# 01_MAIN.net
KiCad netlist of a schematic drawn in Altium Designer
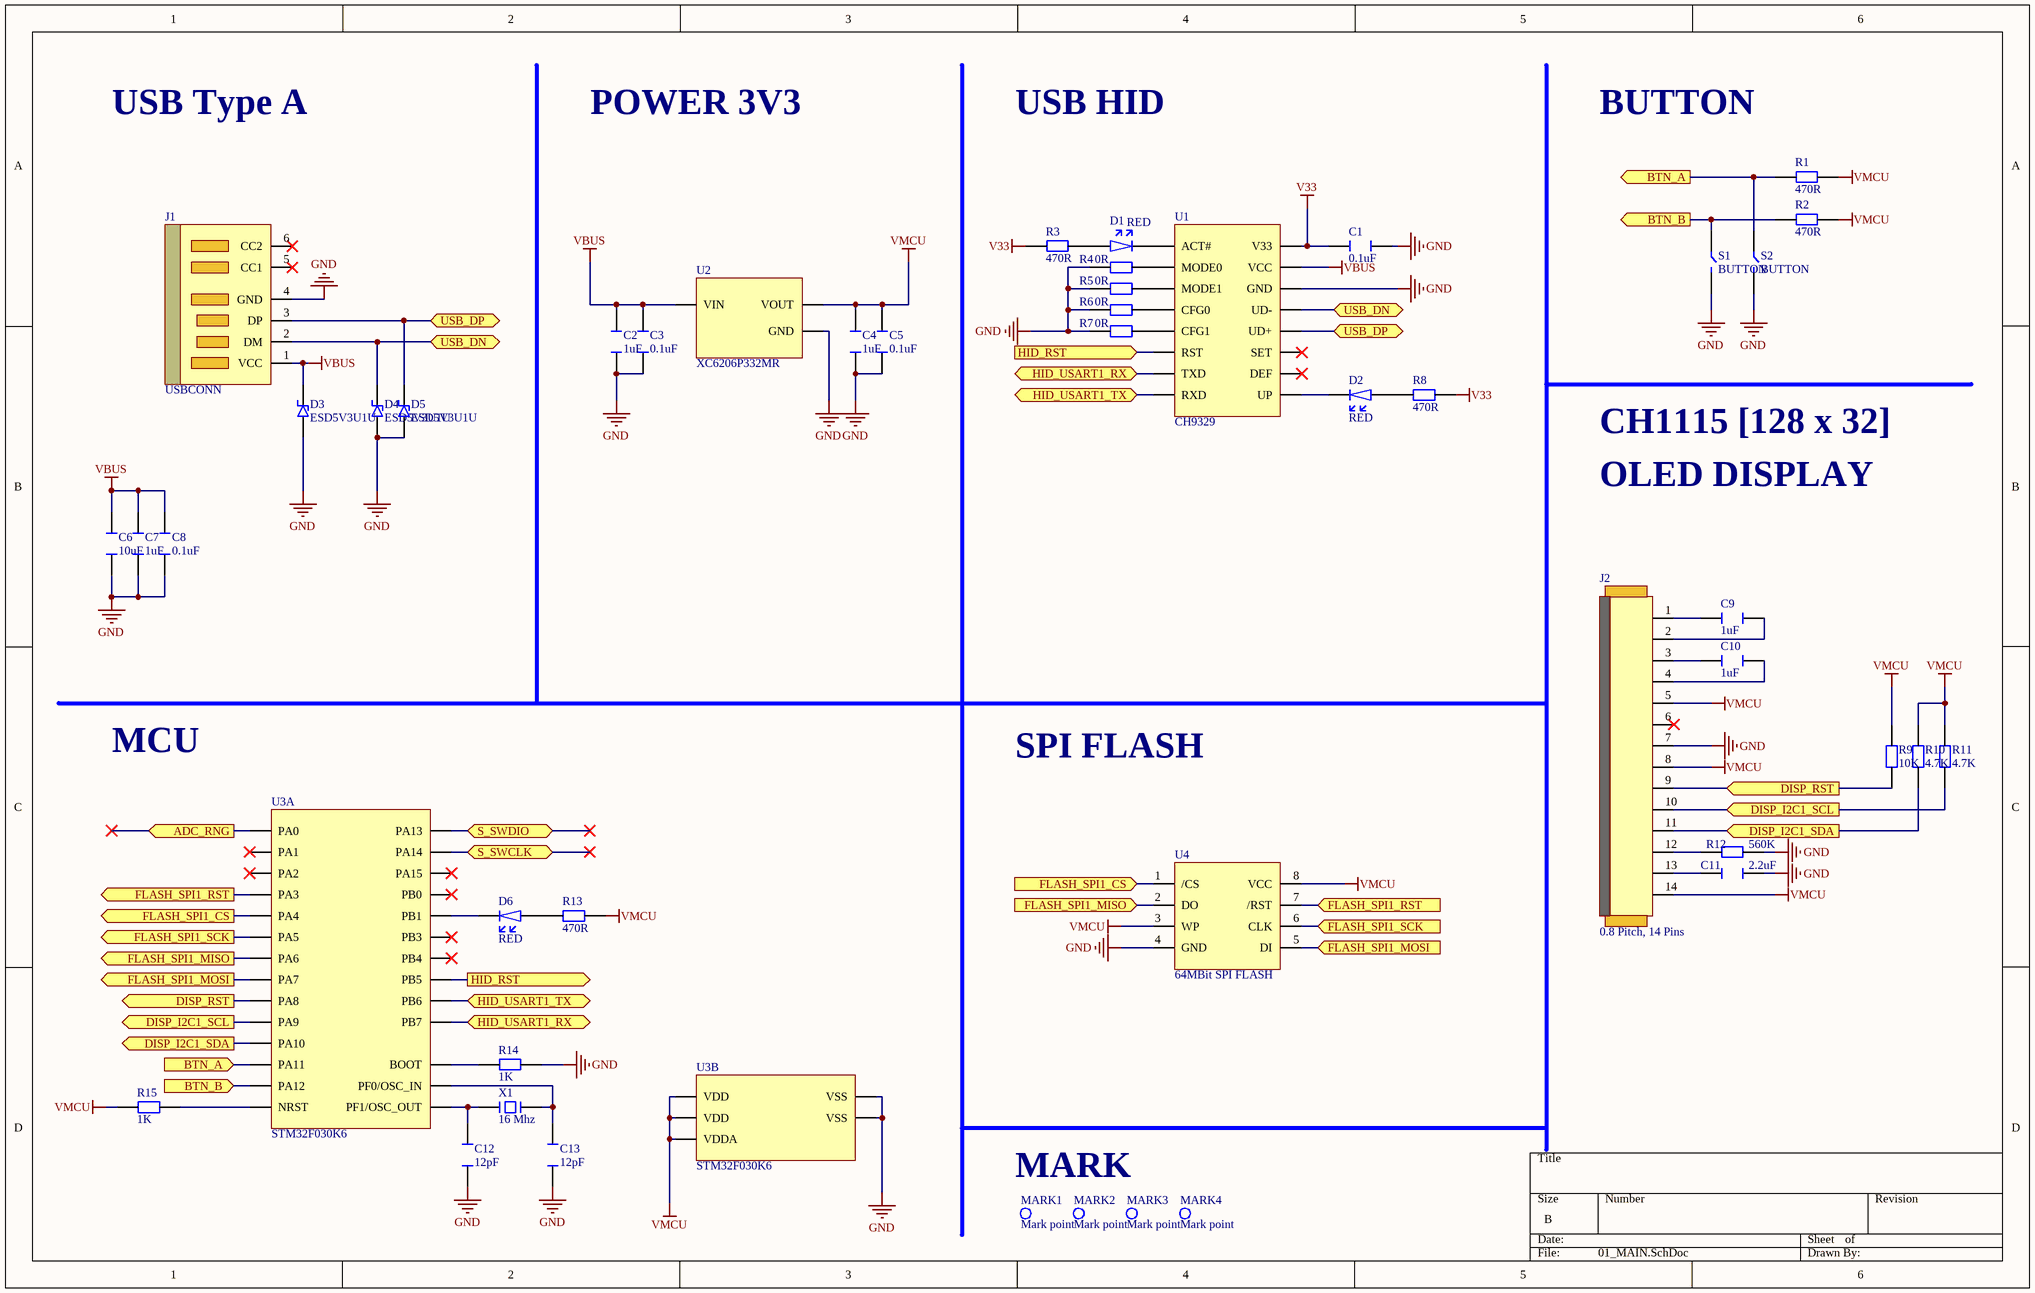
[diagram p0: 01_MAIN.SchDoc]

(export (version "E")
  (design (tool "Eeschema 10.0.6"))
  (components
    (comp (ref "C1") (value "0.1uF") (footprint "C0402") (libsource (lib "Cosmos") (part "C_0.1UF")))
    (comp (ref "C2") (value "1uF") (footprint "C0603") (libsource (lib "Cosmos") (part "C_1UF")))
    (comp (ref "C3") (value "0.1uF") (footprint "C0603") (libsource (lib "Cosmos") (part "C_0.1UF")))
    (comp (ref "C4") (value "1uF") (footprint "C0402") (libsource (lib "Cosmos") (part "C_1UF")))
    (comp (ref "C5") (value "0.1uF") (footprint "C0402") (libsource (lib "Cosmos") (part "C_0.1UF")))
    (comp (ref "C6") (value "10uF") (footprint "C0603") (libsource (lib "Cosmos") (part "C_10UF")))
    (comp (ref "C7") (value "1uF") (footprint "C0603") (libsource (lib "Cosmos") (part "C_1UF")))
    (comp (ref "C8") (value "0.1uF") (footprint "C0603") (libsource (lib "Cosmos") (part "C_0.1UF")))
    (comp (ref "C9") (value "1uF") (footprint "C0402") (libsource (lib "Cosmos") (part "C_1UF")))
    (comp (ref "C10") (value "1uF") (footprint "C0402") (libsource (lib "Cosmos") (part "C_1UF")))
    (comp (ref "C11") (value "2.2uF") (footprint "C0402") (libsource (lib "Cosmos") (part "C_2.2UF")))
    (comp (ref "C12") (value "12pF") (footprint "C0402") (libsource (lib "Cosmos") (part "C_12PF")))
    (comp (ref "C13") (value "12pF") (footprint "C0402") (libsource (lib "Cosmos") (part "C_12PF")))
    (comp (ref "D1") (value "RED") (footprint "LED0402") (libsource (lib "Cosmos") (part "LED_RED")))
    (comp (ref "D2") (value "RED") (footprint "LED0402") (libsource (lib "Cosmos") (part "LED_RED")))
    (comp (ref "D3")
      (value "ESD5V3U1U")
      (footprint "ESD5V3U1U")
      (libsource (lib "Cosmos") (part "ESD5V3U1U"))
    )
    (comp (ref "D4")
      (value "ESD5V3U1U")
      (footprint "ESD5V3U1U")
      (libsource (lib "Cosmos") (part "ESD5V3U1U"))
    )
    (comp (ref "D5")
      (value "ESD5V3U1U")
      (footprint "ESD5V3U1U")
      (libsource (lib "Cosmos") (part "ESD5V3U1U"))
    )
    (comp (ref "D6") (value "RED") (footprint "LED0402") (libsource (lib "Cosmos") (part "LED_RED")))
    (comp (ref "J1")
      (value "USBCONN")
      (footprint "USBAM_SNGLE_8PIN")
      (libsource (lib "Cosmos") (part "USBCONN"))
    )
    (comp (ref "J2")
      (value "0.8 Pitch, 14 Pins")
      (footprint "FPC-14PIN")
      (libsource (lib "Cosmos") (part "FPC_14PIN"))
    )
    (comp (ref "MARK1")
      (value "Mark point")
      (footprint "MARKPOINT")
      (libsource (lib "Earthquake") (part "MP"))
    )
    (comp (ref "MARK2")
      (value "Mark point")
      (footprint "MARKPOINT")
      (libsource (lib "Earthquake") (part "MP"))
    )
    (comp (ref "MARK3")
      (value "Mark point")
      (footprint "MARKPOINT")
      (libsource (lib "Earthquake") (part "MP"))
    )
    (comp (ref "MARK4")
      (value "Mark point")
      (footprint "MARKPOINT")
      (libsource (lib "Earthquake") (part "MP"))
    )
    (comp (ref "R1") (value "470R") (footprint "R0402") (libsource (lib "Cosmos") (part "R_470R")))
    (comp (ref "R2") (value "470R") (footprint "R0402") (libsource (lib "Cosmos") (part "R_470R")))
    (comp (ref "R3") (value "470R") (footprint "R0402") (libsource (lib "Cosmos") (part "R_470R")))
    (comp (ref "R4") (value "0R") (footprint "R0402") (libsource (lib "Cosmos") (part "R_0R")))
    (comp (ref "R5") (value "0R") (footprint "R0402") (libsource (lib "Cosmos") (part "R_0R")))
    (comp (ref "R6") (value "0R") (footprint "R0402") (libsource (lib "Cosmos") (part "R_0R")))
    (comp (ref "R7") (value "0R") (footprint "R0402") (libsource (lib "Cosmos") (part "R_0R")))
    (comp (ref "R8") (value "470R") (footprint "R0402") (libsource (lib "Cosmos") (part "R_470R")))
    (comp (ref "R9") (value "10K") (footprint "R0402") (libsource (lib "Cosmos") (part "R_10K")))
    (comp (ref "R10") (value "4.7K") (footprint "R0402") (libsource (lib "Cosmos") (part "R_4.7K")))
    (comp (ref "R11") (value "4.7K") (footprint "R0402") (libsource (lib "Cosmos") (part "R_4.7K")))
    (comp (ref "R12") (value "560K") (footprint "R0402") (libsource (lib "Cosmos") (part "R_560K")))
    (comp (ref "R13") (value "470R") (footprint "R0402") (libsource (lib "Cosmos") (part "R_470R")))
    (comp (ref "R14") (value "1K") (footprint "R0402") (libsource (lib "Panda") (part "R_1K")))
    (comp (ref "R15") (value "1K") (footprint "R0402") (libsource (lib "Cosmos") (part "R_1K")))
    (comp (ref "S1") (value "BUTTON") (footprint "YD3410") (libsource (lib "Cosmos") (part "BUTTON")))
    (comp (ref "S2") (value "BUTTON") (footprint "YD3410") (libsource (lib "Cosmos") (part "BUTTON")))
    (comp (ref "U1") (value "CH9329") (footprint "CH9329") (libsource (lib "Cosmos") (part "CH9329")))
    (comp (ref "U2")
      (value "XC6206P332MR")
      (footprint "XC6206P332MR")
      (libsource (lib "Cosmos") (part "XC6206P332MR"))
    )
    (comp (ref "U3")
      (value "STM32F030K6")
      (footprint "STM32F030K6")
      (libsource (lib "Cosmos") (part "STM32F030K6"))
    )
    (comp (ref "U4")
      (value "64MBit SPI FLASH")
      (footprint "W25Q64JVSSIQ")
      (libsource (lib "Cosmos") (part "W25Q64JVSSIQ"))
    )
    (comp (ref "X1")
      (value "16 Mhz")
      (footprint "CSTCE16M0V53-R0")
      (libsource (lib "Cosmos") (part "CRYSTAL_16MHZ"))
    )
  )
  (nets
    (net (code "1") (name "/ADC_RNG") (class "Default")
      (node (ref "U3") (pin "6") (pinfunction "PA0_6") (pintype "passive+no_connect"))
    )
    (net (code "2") (name "/BTN_A") (class "Default")
      (node (ref "R1") (pin "1") (pinfunction "17_1") (pintype "passive"))
      (node (ref "S2") (pin "1") (pintype "passive"))
      (node (ref "U3") (pin "21") (pinfunction "PA11_21") (pintype "passive"))
    )
    (net (code "3") (name "/BTN_B") (class "Default")
      (node (ref "R2") (pin "1") (pinfunction "17_1") (pintype "passive"))
      (node (ref "S1") (pin "1") (pintype "passive"))
      (node (ref "U3") (pin "22") (pinfunction "PA12_22") (pintype "passive"))
    )
    (net (code "4") (name "/DISP_I2C1_SCL") (class "Default")
      (node (ref "J2") (pin "10") (pintype "passive"))
      (node (ref "R11") (pin "1") (pinfunction "17_1") (pintype "passive"))
      (node (ref "U3") (pin "19") (pinfunction "PA9_19") (pintype "passive"))
    )
    (net (code "5") (name "/DISP_I2C1_SDA") (class "Default")
      (node (ref "J2") (pin "11") (pintype "passive"))
      (node (ref "R10") (pin "1") (pinfunction "17_1") (pintype "passive"))
      (node (ref "U3") (pin "20") (pinfunction "PA10_20") (pintype "passive"))
    )
    (net (code "6") (name "/DISP_RST") (class "Default")
      (node (ref "J2") (pin "9") (pintype "passive"))
      (node (ref "R9") (pin "1") (pinfunction "17_1") (pintype "passive"))
      (node (ref "U3") (pin "18") (pinfunction "PA8_18") (pintype "passive"))
    )
    (net (code "7") (name "/FLASH_SPI1_CS") (class "Default")
      (node (ref "U3") (pin "10") (pinfunction "PA4_10") (pintype "passive"))
      (node (ref "U4") (pin "1") (pinfunction "/CS_1") (pintype "passive"))
    )
    (net (code "8") (name "/FLASH_SPI1_MISO") (class "Default")
      (node (ref "U3") (pin "12") (pinfunction "PA6_12") (pintype "passive"))
      (node (ref "U4") (pin "2") (pinfunction "DO_2") (pintype "passive"))
    )
    (net (code "9") (name "/FLASH_SPI1_MOSI") (class "Default")
      (node (ref "U3") (pin "13") (pinfunction "PA7_13") (pintype "passive"))
      (node (ref "U4") (pin "5") (pinfunction "DI_5") (pintype "passive"))
    )
    (net (code "10") (name "/FLASH_SPI1_RST") (class "Default")
      (node (ref "U3") (pin "9") (pinfunction "PA3_9") (pintype "passive"))
      (node (ref "U4") (pin "7") (pinfunction "/RST_7") (pintype "passive"))
    )
    (net (code "11") (name "/FLASH_SPI1_SCK") (class "Default")
      (node (ref "U3") (pin "11") (pinfunction "PA5_11") (pintype "passive"))
      (node (ref "U4") (pin "6") (pinfunction "CLK_6") (pintype "passive"))
    )
    (net (code "12") (name "/HID_RST") (class "Default")
      (node (ref "U1") (pin "6") (pinfunction "RST_6") (pintype "passive"))
      (node (ref "U3") (pin "28") (pinfunction "PB5_28") (pintype "passive"))
    )
    (net (code "13") (name "/HID_USART1_RX") (class "Default")
      (node (ref "U1") (pin "7") (pinfunction "TXD_7") (pintype "passive"))
      (node (ref "U3") (pin "30") (pinfunction "PB7_30") (pintype "passive"))
    )
    (net (code "14") (name "/HID_USART1_TX") (class "Default")
      (node (ref "U1") (pin "8") (pinfunction "RXD_8") (pintype "passive"))
      (node (ref "U3") (pin "29") (pinfunction "PB6_29") (pintype "passive"))
    )
    (net (code "15") (name "/S_SWCLK") (class "Default")
      (node (ref "U3") (pin "24") (pinfunction "PA14_24") (pintype "passive+no_connect"))
    )
    (net (code "16") (name "/S_SWDIO") (class "Default")
      (node (ref "U3") (pin "23") (pinfunction "PA13_23") (pintype "passive+no_connect"))
    )
    (net (code "17") (name "/USB_DN") (class "Default")
      (node (ref "D4") (pin "2") (pinfunction "18_2") (pintype "passive"))
      (node (ref "J1") (pin "2") (pinfunction "DM_2") (pintype "passive"))
      (node (ref "U1") (pin "13") (pinfunction "UD-_13") (pintype "passive"))
    )
    (net (code "18") (name "/USB_DP") (class "Default")
      (node (ref "D5") (pin "2") (pinfunction "18_2") (pintype "passive"))
      (node (ref "J1") (pin "3") (pinfunction "DP_3") (pintype "passive"))
      (node (ref "U1") (pin "12") (pinfunction "UD+_12") (pintype "passive"))
    )
    (net (code "19") (name "GND") (class "Default")
      (node (ref "C1") (pin "2") (pinfunction "18_2") (pintype "passive"))
      (node (ref "C11") (pin "2") (pinfunction "18_2") (pintype "passive"))
      (node (ref "C12") (pin "1") (pinfunction "17_1") (pintype "passive"))
      (node (ref "C13") (pin "1") (pinfunction "17_1") (pintype "passive"))
      (node (ref "C2") (pin "1") (pinfunction "17_1") (pintype "passive"))
      (node (ref "C3") (pin "1") (pinfunction "17_1") (pintype "passive"))
      (node (ref "C4") (pin "1") (pinfunction "17_1") (pintype "passive"))
      (node (ref "C5") (pin "1") (pinfunction "17_1") (pintype "passive"))
      (node (ref "C6") (pin "1") (pinfunction "17_1") (pintype "passive"))
      (node (ref "C7") (pin "1") (pinfunction "17_1") (pintype "passive"))
      (node (ref "C8") (pin "1") (pinfunction "17_1") (pintype "passive"))
      (node (ref "D3") (pin "1") (pinfunction "17_1") (pintype "passive"))
      (node (ref "D4") (pin "1") (pinfunction "17_1") (pintype "passive"))
      (node (ref "D5") (pin "1") (pinfunction "17_1") (pintype "passive"))
      (node (ref "J1") (pin "4") (pinfunction "GND_4") (pintype "passive"))
      (node (ref "J2") (pin "7") (pintype "passive"))
      (node (ref "R12") (pin "2") (pinfunction "18_2") (pintype "passive"))
      (node (ref "R14") (pin "2") (pinfunction "18_2") (pintype "passive"))
      (node (ref "R4") (pin "1") (pinfunction "17_1") (pintype "passive"))
      (node (ref "R5") (pin "1") (pinfunction "17_1") (pintype "passive"))
      (node (ref "R6") (pin "1") (pinfunction "17_1") (pintype "passive"))
      (node (ref "R7") (pin "1") (pinfunction "17_1") (pintype "passive"))
      (node (ref "S1") (pin "2") (pintype "passive"))
      (node (ref "S2") (pin "2") (pintype "passive"))
      (node (ref "U1") (pin "14") (pinfunction "GND_14") (pintype "passive"))
      (node (ref "U2") (pin "1") (pinfunction "GND_1") (pintype "passive"))
      (node (ref "U3") (pin "16") (pinfunction "VSS_16") (pintype "passive"))
      (node (ref "U3") (pin "32") (pinfunction "VSS_32") (pintype "passive"))
      (node (ref "U4") (pin "4") (pinfunction "GND_4") (pintype "passive"))
    )
    (net (code "20") (name "Net-(C9-17)") (class "Default")
      (node (ref "C9") (pin "1") (pinfunction "17_1") (pintype "passive"))
      (node (ref "J2") (pin "1") (pintype "passive"))
    )
    (net (code "21") (name "Net-(C9-18)") (class "Default")
      (node (ref "C9") (pin "2") (pinfunction "18_2") (pintype "passive"))
      (node (ref "J2") (pin "2") (pintype "passive"))
    )
    (net (code "22") (name "Net-(C10-17)") (class "Default")
      (node (ref "C10") (pin "1") (pinfunction "17_1") (pintype "passive"))
      (node (ref "J2") (pin "3") (pintype "passive"))
    )
    (net (code "23") (name "Net-(C10-18)") (class "Default")
      (node (ref "C10") (pin "2") (pinfunction "18_2") (pintype "passive"))
      (node (ref "J2") (pin "4") (pintype "passive"))
    )
    (net (code "24") (name "Net-(C11-17)") (class "Default")
      (node (ref "C11") (pin "1") (pinfunction "17_1") (pintype "passive"))
      (node (ref "J2") (pin "13") (pintype "passive"))
    )
    (net (code "25") (name "Net-(C12-18)") (class "Default")
      (node (ref "C12") (pin "2") (pinfunction "18_2") (pintype "passive"))
      (node (ref "U3") (pin "3") (pinfunction "PF1/OSC_OUT_3") (pintype "passive"))
      (node (ref "X1") (pin "1") (pinfunction "5_1") (pintype "passive"))
    )
    (net (code "26") (name "Net-(C13-18)") (class "Default")
      (node (ref "C13") (pin "2") (pinfunction "18_2") (pintype "passive"))
      (node (ref "U3") (pin "2") (pinfunction "PF0/OSC_IN_2") (pintype "passive"))
      (node (ref "X1") (pin "2") (pinfunction "6_2") (pintype "passive"))
    )
    (net (code "27") (name "Net-(R3-18)") (class "Default")
      (node (ref "D1") (pin "1") (pinfunction "1_1") (pintype "passive"))
      (node (ref "R3") (pin "2") (pinfunction "18_2") (pintype "passive"))
    )
    (net (code "28") (name "Net-(R4-18)") (class "Default")
      (node (ref "R4") (pin "2") (pinfunction "18_2") (pintype "passive"))
      (node (ref "U1") (pin "2") (pinfunction "MODE0_2") (pintype "passive"))
    )
    (net (code "29") (name "Net-(R5-18)") (class "Default")
      (node (ref "R5") (pin "2") (pinfunction "18_2") (pintype "passive"))
      (node (ref "U1") (pin "3") (pinfunction "MODE1_3") (pintype "passive"))
    )
    (net (code "30") (name "Net-(R6-18)") (class "Default")
      (node (ref "R6") (pin "2") (pinfunction "18_2") (pintype "passive"))
      (node (ref "U1") (pin "4") (pinfunction "CFG0_4") (pintype "passive"))
    )
    (net (code "31") (name "Net-(R7-18)") (class "Default")
      (node (ref "R7") (pin "2") (pinfunction "18_2") (pintype "passive"))
      (node (ref "U1") (pin "5") (pinfunction "CFG1_5") (pintype "passive"))
    )
    (net (code "32") (name "Net-(R8-17)") (class "Default")
      (node (ref "D2") (pin "1") (pinfunction "1_1") (pintype "passive"))
      (node (ref "R8") (pin "1") (pinfunction "17_1") (pintype "passive"))
    )
    (net (code "33") (name "Net-(R12-17)") (class "Default")
      (node (ref "J2") (pin "12") (pintype "passive"))
      (node (ref "R12") (pin "1") (pinfunction "17_1") (pintype "passive"))
    )
    (net (code "34") (name "Net-(R13-17)") (class "Default")
      (node (ref "D6") (pin "1") (pinfunction "1_1") (pintype "passive"))
      (node (ref "R13") (pin "1") (pinfunction "17_1") (pintype "passive"))
    )
    (net (code "35") (name "Net-(R14-17)") (class "Default")
      (node (ref "R14") (pin "1") (pinfunction "17_1") (pintype "passive"))
      (node (ref "U3") (pin "31") (pinfunction "BOOT_31") (pintype "passive"))
    )
    (net (code "36") (name "Net-(R15-18)") (class "Default")
      (node (ref "R15") (pin "2") (pinfunction "18_2") (pintype "passive"))
      (node (ref "U3") (pin "4") (pinfunction "NRST_4") (pintype "passive"))
    )
    (net (code "37") (name "Net-(U1-ACT#)") (class "Default")
      (node (ref "D1") (pin "2") (pinfunction "2_2") (pintype "passive"))
      (node (ref "U1") (pin "1") (pinfunction "ACT#_1") (pintype "passive"))
    )
    (net (code "38") (name "Net-(U1-UP)") (class "Default")
      (node (ref "D2") (pin "2") (pinfunction "2_2") (pintype "passive"))
      (node (ref "U1") (pin "9") (pinfunction "UP_9") (pintype "passive"))
    )
    (net (code "39") (name "Net-(U3A-PB1)") (class "Default")
      (node (ref "D6") (pin "2") (pinfunction "2_2") (pintype "passive"))
      (node (ref "U3") (pin "15") (pinfunction "PB1_15") (pintype "passive"))
    )
    (net (code "40") (name "V33") (class "Default")
      (node (ref "C1") (pin "1") (pinfunction "17_1") (pintype "passive"))
      (node (ref "R3") (pin "1") (pinfunction "17_1") (pintype "passive"))
      (node (ref "R8") (pin "2") (pinfunction "18_2") (pintype "passive"))
      (node (ref "U1") (pin "16") (pinfunction "V33_16") (pintype "passive"))
    )
    (net (code "41") (name "VBUS") (class "Default")
      (node (ref "C2") (pin "2") (pinfunction "18_2") (pintype "passive"))
      (node (ref "C3") (pin "2") (pinfunction "18_2") (pintype "passive"))
      (node (ref "C6") (pin "2") (pinfunction "18_2") (pintype "passive"))
      (node (ref "C7") (pin "2") (pinfunction "18_2") (pintype "passive"))
      (node (ref "C8") (pin "2") (pinfunction "18_2") (pintype "passive"))
      (node (ref "D3") (pin "2") (pinfunction "18_2") (pintype "passive"))
      (node (ref "J1") (pin "1") (pinfunction "VCC_1") (pintype "passive"))
      (node (ref "U1") (pin "15") (pinfunction "VCC_15") (pintype "passive"))
      (node (ref "U2") (pin "3") (pinfunction "VIN_3") (pintype "passive"))
    )
    (net (code "42") (name "VMCU") (class "Default")
      (node (ref "C4") (pin "2") (pinfunction "18_2") (pintype "passive"))
      (node (ref "C5") (pin "2") (pinfunction "18_2") (pintype "passive"))
      (node (ref "J2") (pin "14") (pintype "passive"))
      (node (ref "J2") (pin "5") (pintype "passive"))
      (node (ref "J2") (pin "8") (pintype "passive"))
      (node (ref "R1") (pin "2") (pinfunction "18_2") (pintype "passive"))
      (node (ref "R10") (pin "2") (pinfunction "18_2") (pintype "passive"))
      (node (ref "R11") (pin "2") (pinfunction "18_2") (pintype "passive"))
      (node (ref "R13") (pin "2") (pinfunction "18_2") (pintype "passive"))
      (node (ref "R15") (pin "1") (pinfunction "17_1") (pintype "passive"))
      (node (ref "R2") (pin "2") (pinfunction "18_2") (pintype "passive"))
      (node (ref "R9") (pin "2") (pinfunction "18_2") (pintype "passive"))
      (node (ref "U2") (pin "2") (pinfunction "VOUT_2") (pintype "passive"))
      (node (ref "U3") (pin "1") (pinfunction "VDD_1") (pintype "passive"))
      (node (ref "U3") (pin "17") (pinfunction "VDD_17") (pintype "passive"))
      (node (ref "U3") (pin "5") (pinfunction "VDDA_5") (pintype "passive"))
      (node (ref "U4") (pin "3") (pinfunction "WP_3") (pintype "passive"))
      (node (ref "U4") (pin "8") (pinfunction "VCC_8") (pintype "passive"))
    )
    (net (code "43") (name "unconnected-(J1-CC1-Pad5)") (class "Default")
      (node (ref "J1") (pin "5") (pinfunction "CC1_5") (pintype "passive+no_connect"))
    )
    (net (code "44") (name "unconnected-(J1-CC2-Pad6)") (class "Default")
      (node (ref "J1") (pin "6") (pinfunction "CC2_6") (pintype "passive+no_connect"))
    )
    (net (code "45") (name "unconnected-(J2-Pad6)") (class "Default")
      (node (ref "J2") (pin "6") (pintype "passive+no_connect"))
    )
    (net (code "46") (name "unconnected-(U1-DEF-Pad10)") (class "Default")
      (node (ref "U1") (pin "10") (pinfunction "DEF_10") (pintype "passive+no_connect"))
    )
    (net (code "47") (name "unconnected-(U1-SET-Pad11)") (class "Default")
      (node (ref "U1") (pin "11") (pinfunction "SET_11") (pintype "passive+no_connect"))
    )
    (net (code "48") (name "unconnected-(U3A-PA1-Pad7)") (class "Default")
      (node (ref "U3") (pin "7") (pinfunction "PA1_7") (pintype "passive+no_connect"))
    )
    (net (code "49") (name "unconnected-(U3A-PA2-Pad8)") (class "Default")
      (node (ref "U3") (pin "8") (pinfunction "PA2_8") (pintype "passive+no_connect"))
    )
    (net (code "50") (name "unconnected-(U3A-PA15-Pad25)") (class "Default")
      (node (ref "U3") (pin "25") (pinfunction "PA15_25") (pintype "passive+no_connect"))
    )
    (net (code "51") (name "unconnected-(U3A-PB0-Pad14)") (class "Default")
      (node (ref "U3") (pin "14") (pinfunction "PB0_14") (pintype "passive+no_connect"))
    )
    (net (code "52") (name "unconnected-(U3A-PB3-Pad26)") (class "Default")
      (node (ref "U3") (pin "26") (pinfunction "PB3_26") (pintype "passive+no_connect"))
    )
    (net (code "53") (name "unconnected-(U3A-PB4-Pad27)") (class "Default")
      (node (ref "U3") (pin "27") (pinfunction "PB4_27") (pintype "passive+no_connect"))
    )
  )
)
